# Power_2.net
KiCad netlist of a schematic drawn in Altium Designer
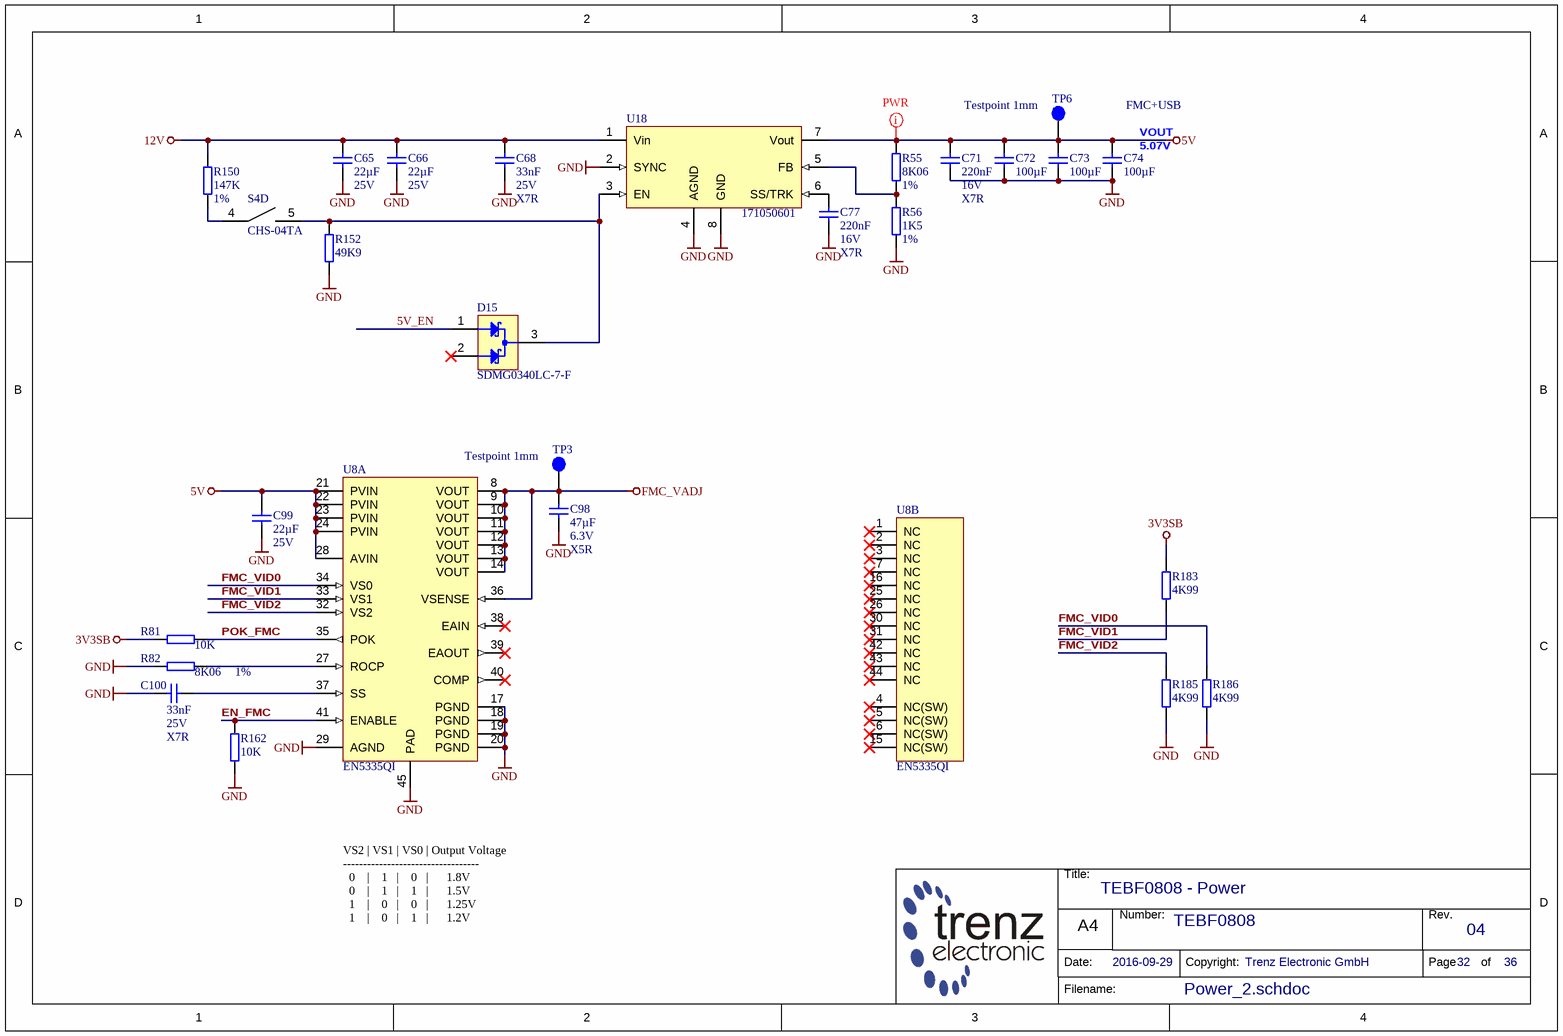
[diagram p0: Power_2.schdoc]

(export (version "E")
  (design (tool "Eeschema 10.0.6"))
  (components
    (comp (ref "C65")
      (value "22µF")
      (footprint "CAPC3216X180N")
      (description "KON 22µF X5R 25V SMD 10%")
      (fields (field (name "VOLTAGE") "25V") (field (name "TOLERANCE") "10%"))
      (libsource (lib "TE") (part "CAP-NP"))
    )
    (comp (ref "C66")
      (value "22µF")
      (footprint "CAPC3216X180N")
      (description "KON 22µF X5R 25V SMD 10%")
      (fields (field (name "VOLTAGE") "25V") (field (name "TOLERANCE") "10%"))
      (libsource (lib "TE") (part "CAP-NP"))
    )
    (comp (ref "C68")
      (value "33nF")
      (footprint "CAPC1005X55N")
      (description "KON 33nF 25V X7R SMD")
      (fields (field (name "VOLTAGE") "25V") (field (name "TECHNOLOGY") "X7R"))
      (libsource (lib "TE") (part "CAP-NP"))
    )
    (comp (ref "C71")
      (value "220nF")
      (footprint "CAPC1005X55N")
      (description "KON 220nF 16V X7R SMD")
      (fields (field (name "VOLTAGE") "16V") (field (name "TECHNOLOGY") "X7R"))
      (libsource (lib "TE") (part "CAP-NP"))
    )
    (comp (ref "C72")
      (value "100µF")
      (footprint "CAPC3216X180N")
      (description "KON 100µF 6,3V X5R SMD 20%")
      (fields (field (name "TOLERANCE") "20%") (field (name "VOLTAGE") "6.3V"))
      (libsource (lib "TE") (part "CAP-NP"))
    )
    (comp (ref "C73")
      (value "100µF")
      (footprint "CAPC3216X180N")
      (description "KON 100µF 6,3V X5R SMD 20%")
      (fields (field (name "TOLERANCE") "20%") (field (name "VOLTAGE") "6.3V"))
      (libsource (lib "TE") (part "CAP-NP"))
    )
    (comp (ref "C74")
      (value "100µF")
      (footprint "CAPC3216X180N")
      (description "KON 100µF 6,3V X5R SMD 20%")
      (fields (field (name "TOLERANCE") "20%") (field (name "VOLTAGE") "6.3V"))
      (libsource (lib "TE") (part "CAP-NP"))
    )
    (comp (ref "C77")
      (value "220nF")
      (footprint "CAPC1005X55N")
      (description "KON 220nF 16V X7R SMD")
      (fields (field (name "VOLTAGE") "16V") (field (name "TECHNOLOGY") "X7R"))
      (libsource (lib "TE") (part "CAP-NP"))
    )
    (comp (ref "C98")
      (value "47µF")
      (footprint "CAPC3216X180N")
      (description "KON 47µF 6.3V  X5R SMD 20%")
      (fields
        (field (name "VOLTAGE") "6.3V")
        (field (name "TECHNOLOGY") "X5R")
        (field (name "TOLERANCE") "20%")
      )
      (libsource (lib "TE") (part "CAP-NP"))
    )
    (comp (ref "C99")
      (value "22µF")
      (footprint "CAPC3216X180N")
      (description "KON 22µF X5R 25V SMD 10%")
      (fields (field (name "VOLTAGE") "25V") (field (name "TOLERANCE") "10%"))
      (libsource (lib "TE") (part "CAP-NP"))
    )
    (comp (ref "C100")
      (value "33nF")
      (footprint "CAPC1005X55N")
      (description "KON 33nF 25V X7R SMD")
      (fields (field (name "VOLTAGE") "25V") (field (name "TECHNOLOGY") "X7R"))
      (libsource (lib "TE") (part "CAP-NP"))
    )
    (comp (ref "D15")
      (value "SDMG0340LC-7-F")
      (footprint "SOT65P210X110-3N")
      (libsource (lib "TE") (part "SDMG0340LC"))
    )
    (comp (ref "R55")
      (value "8K06")
      (footprint "RESC1005X40N")
      (description "WID SMD 8K06 1% 0,063W")
      (fields (field (name "TOLERANCE") "1%"))
      (libsource (lib "TE") (part "RES"))
    )
    (comp (ref "R56")
      (value "1K5")
      (footprint "RESC1005X40N")
      (description "WID SMD 1K5 1% 0,063W")
      (fields (field (name "TOLERANCE") "1%"))
      (libsource (lib "TE") (part "RES"))
    )
    (comp (ref "R81")
      (value "10K")
      (footprint "RESC1005X40N")
      (description "WID SMD 10K 1% 0,063W")
      (fields (field (name "TOLERANCE") "1%"))
      (libsource (lib "TE") (part "RES"))
    )
    (comp (ref "R82")
      (value "8K06")
      (footprint "RESC1005X40N")
      (description "WID SMD 8K06 1% 0,063W")
      (fields (field (name "TOLERANCE") "1%"))
      (libsource (lib "TE") (part "RES"))
    )
    (comp (ref "R150")
      (value "147K")
      (footprint "RESC1005X40N")
      (description "WID SMD 147K 1% 0,063W")
      (fields (field (name "TOLERANCE") "1%"))
      (libsource (lib "TE") (part "RES"))
    )
    (comp (ref "R152")
      (value "49K9")
      (footprint "RESC1005X40N")
      (description "WID SMD 49K9 1% 0,063W")
      (fields (field (name "TOLERANCE") "1%"))
      (libsource (lib "TE") (part "RES"))
    )
    (comp (ref "R162")
      (value "10K")
      (footprint "RESC1005X40N")
      (description "WID SMD 10K 1% 0,063W")
      (fields (field (name "TOLERANCE") "1%"))
      (libsource (lib "TE") (part "RES"))
    )
    (comp (ref "R183")
      (value "4K99")
      (footprint "RESC1005X40N")
      (description "WID SMD 4K99 1% 0,063W")
      (fields (field (name "TOLERANCE") "1%"))
      (libsource (lib "TE") (part "RES"))
    )
    (comp (ref "R185")
      (value "4K99")
      (footprint "RESC1005X40N")
      (description "WID SMD 4K99 1% 0,063W")
      (fields (field (name "TOLERANCE") "1%"))
      (libsource (lib "TE") (part "RES"))
    )
    (comp (ref "R186")
      (value "4K99")
      (footprint "RESC1005X40N")
      (description "WID SMD 4K99 1% 0,063W")
      (fields (field (name "TOLERANCE") "1%"))
      (libsource (lib "TE") (part "RES"))
    )
    (comp (ref "S4")
      (value "CHS-04TA")
      (footprint "CHS-04TA")
      (description "DIP Schalter 4 fach 1,27mm SMD")
      (libsource (lib "TE") (part "CHS-04TA"))
    )
    (comp (ref "TP3") (value "Testpoint 1mm") (footprint "TP_1mm") (libsource (lib "TE") (part "TP")))
    (comp (ref "TP6") (value "Testpoint 1mm") (footprint "TP_1mm") (libsource (lib "TE") (part "TP")))
    (comp (ref "U8") (value "EN5335QI") (footprint "EN5335QI") (libsource (lib "TE") (part "EN5335QI")))
    (comp (ref "U18")
      (value "171050601")
      (footprint "7TO-PMOD")
      (libsource (lib "TE") (part "WE-DCDC-171050601"))
    )
  )
  (nets
    (net (code "1") (name "/5V_EN") (class "Default")
      (node (ref "D15") (pin "1") (pinfunction "A_1") (pintype "passive"))
    )
    (net (code "2") (name "/EN_FMC") (class "Default")
      (node (ref "R162") (pin "2") (pinfunction "2_2") (pintype "passive"))
      (node (ref "U8") (pin "41") (pinfunction "ENABLE_41") (pintype "input"))
    )
    (net (code "3") (name "/FMC_VID0") (class "Default")
      (node (ref "R186") (pin "1") (pinfunction "1_1") (pintype "passive"))
      (node (ref "U8") (pin "34") (pinfunction "VS0_34") (pintype "input"))
    )
    (net (code "4") (name "/FMC_VID1") (class "Default")
      (node (ref "R183") (pin "2") (pinfunction "2_2") (pintype "passive"))
      (node (ref "U8") (pin "33") (pinfunction "VS1_33") (pintype "input"))
    )
    (net (code "5") (name "/FMC_VID2") (class "Default")
      (node (ref "R185") (pin "1") (pinfunction "1_1") (pintype "passive"))
      (node (ref "U8") (pin "32") (pinfunction "VS2_32") (pintype "input"))
    )
    (net (code "6") (name "/POK_FMC") (class "Default")
      (node (ref "R81") (pin "2") (pinfunction "2_2") (pintype "passive"))
      (node (ref "U8") (pin "35") (pinfunction "POK_35") (pintype "output"))
    )
    (net (code "7") (name "3V3SB") (class "Default")
      (node (ref "R183") (pin "1") (pinfunction "1_1") (pintype "passive"))
      (node (ref "R81") (pin "1") (pinfunction "1_1") (pintype "passive"))
    )
    (net (code "8") (name "5V") (class "Default")
      (node (ref "C71") (pin "1") (pinfunction "1_1") (pintype "passive"))
      (node (ref "C72") (pin "1") (pinfunction "1_1") (pintype "passive"))
      (node (ref "C73") (pin "1") (pinfunction "1_1") (pintype "passive"))
      (node (ref "C74") (pin "1") (pinfunction "1_1") (pintype "passive"))
      (node (ref "C99") (pin "2") (pinfunction "2_2") (pintype "passive"))
      (node (ref "R55") (pin "1") (pinfunction "1_1") (pintype "passive"))
      (node (ref "TP6") (pin "1") (pintype "passive"))
      (node (ref "U18") (pin "7") (pinfunction "Vout_7") (pintype "power_in"))
      (node (ref "U8") (pin "21") (pinfunction "PVIN_21") (pintype "power_in"))
      (node (ref "U8") (pin "22") (pinfunction "PVIN_22") (pintype "power_in"))
      (node (ref "U8") (pin "23") (pinfunction "PVIN_23") (pintype "power_in"))
      (node (ref "U8") (pin "24") (pinfunction "PVIN_24") (pintype "power_in"))
      (node (ref "U8") (pin "28") (pinfunction "AVIN_28") (pintype "power_in"))
    )
    (net (code "9") (name "12V") (class "Default")
      (node (ref "C65") (pin "2") (pinfunction "2_2") (pintype "passive"))
      (node (ref "C66") (pin "2") (pinfunction "2_2") (pintype "passive"))
      (node (ref "C68") (pin "1") (pinfunction "1_1") (pintype "passive"))
      (node (ref "R150") (pin "2") (pinfunction "2_2") (pintype "passive"))
      (node (ref "U18") (pin "1") (pinfunction "Vin_1") (pintype "power_in"))
    )
    (net (code "10") (name "FMC_VADJ") (class "Default")
      (node (ref "C98") (pin "1") (pinfunction "1_1") (pintype "passive"))
      (node (ref "TP3") (pin "1") (pintype "passive"))
      (node (ref "U8") (pin "10") (pinfunction "VOUT_10") (pintype "power_in"))
      (node (ref "U8") (pin "11") (pinfunction "VOUT_11") (pintype "power_in"))
      (node (ref "U8") (pin "12") (pinfunction "VOUT_12") (pintype "power_in"))
      (node (ref "U8") (pin "13") (pinfunction "VOUT_13") (pintype "power_in"))
      (node (ref "U8") (pin "14") (pinfunction "VOUT_14") (pintype "power_in"))
      (node (ref "U8") (pin "36") (pinfunction "VSENSE_36") (pintype "input"))
      (node (ref "U8") (pin "8") (pinfunction "VOUT_8") (pintype "power_in"))
      (node (ref "U8") (pin "9") (pinfunction "VOUT_9") (pintype "power_in"))
    )
    (net (code "11") (name "GND") (class "Default")
      (node (ref "C100") (pin "1") (pinfunction "1_1") (pintype "passive"))
      (node (ref "C65") (pin "1") (pinfunction "1_1") (pintype "passive"))
      (node (ref "C66") (pin "1") (pinfunction "1_1") (pintype "passive"))
      (node (ref "C68") (pin "2") (pinfunction "2_2") (pintype "passive"))
      (node (ref "C71") (pin "2") (pinfunction "2_2") (pintype "passive"))
      (node (ref "C72") (pin "2") (pinfunction "2_2") (pintype "passive"))
      (node (ref "C73") (pin "2") (pinfunction "2_2") (pintype "passive"))
      (node (ref "C74") (pin "2") (pinfunction "2_2") (pintype "passive"))
      (node (ref "C77") (pin "2") (pinfunction "2_2") (pintype "passive"))
      (node (ref "C98") (pin "2") (pinfunction "2_2") (pintype "passive"))
      (node (ref "C99") (pin "1") (pinfunction "1_1") (pintype "passive"))
      (node (ref "R152") (pin "2") (pinfunction "2_2") (pintype "passive"))
      (node (ref "R162") (pin "1") (pinfunction "1_1") (pintype "passive"))
      (node (ref "R185") (pin "2") (pinfunction "2_2") (pintype "passive"))
      (node (ref "R186") (pin "2") (pinfunction "2_2") (pintype "passive"))
      (node (ref "R56") (pin "2") (pinfunction "2_2") (pintype "passive"))
      (node (ref "R82") (pin "1") (pinfunction "1_1") (pintype "passive"))
      (node (ref "U18") (pin "2") (pinfunction "SYNC_2") (pintype "input"))
      (node (ref "U18") (pin "4") (pinfunction "AGND_4") (pintype "power_in"))
      (node (ref "U18") (pin "8") (pinfunction "GND_8") (pintype "power_in"))
      (node (ref "U8") (pin "17") (pinfunction "PGND_17") (pintype "power_in"))
      (node (ref "U8") (pin "18") (pinfunction "PGND_18") (pintype "power_in"))
      (node (ref "U8") (pin "19") (pinfunction "PGND_19") (pintype "power_in"))
      (node (ref "U8") (pin "20") (pinfunction "PGND_20") (pintype "power_in"))
      (node (ref "U8") (pin "29") (pinfunction "AGND_29") (pintype "power_in"))
      (node (ref "U8") (pin "45") (pinfunction "PAD_45") (pintype "passive"))
    )
    (net (code "12") (name "Net-(D15-K)") (class "Default")
      (node (ref "D15") (pin "3") (pinfunction "K_3") (pintype "passive"))
      (node (ref "R152") (pin "1") (pinfunction "1_1") (pintype "passive"))
      (node (ref "S4") (pin "5") (pinfunction "5_5") (pintype "passive"))
      (node (ref "U18") (pin "3") (pinfunction "EN_3") (pintype "input"))
    )
    (net (code "13") (name "Net-(R150-Pad1)") (class "Default")
      (node (ref "R150") (pin "1") (pinfunction "1_1") (pintype "passive"))
      (node (ref "S4") (pin "4") (pinfunction "4_4") (pintype "passive"))
    )
    (net (code "14") (name "Net-(U8A-ROCP)") (class "Default")
      (node (ref "R82") (pin "2") (pinfunction "2_2") (pintype "passive"))
      (node (ref "U8") (pin "27") (pinfunction "ROCP_27") (pintype "input"))
    )
    (net (code "15") (name "Net-(U8A-SS)") (class "Default")
      (node (ref "C100") (pin "2") (pinfunction "2_2") (pintype "passive"))
      (node (ref "U8") (pin "37") (pinfunction "SS_37") (pintype "input"))
    )
    (net (code "16") (name "Net-(U18-FB)") (class "Default")
      (node (ref "R55") (pin "2") (pinfunction "2_2") (pintype "passive"))
      (node (ref "R56") (pin "1") (pinfunction "1_1") (pintype "passive"))
      (node (ref "U18") (pin "5") (pinfunction "FB_5") (pintype "input"))
    )
    (net (code "17") (name "Net-(U18-SS{slash}TRK)") (class "Default")
      (node (ref "C77") (pin "1") (pinfunction "1_1") (pintype "passive"))
      (node (ref "U18") (pin "6") (pinfunction "SS/TRK_6") (pintype "input"))
    )
    (net (code "18") (name "unconnected-(D15-A-Pad2)") (class "Default")
      (node (ref "D15") (pin "2") (pinfunction "A_2") (pintype "passive+no_connect"))
    )
    (net (code "19") (name "unconnected-(U8A-COMP-Pad40)") (class "Default")
      (node (ref "U8") (pin "40") (pinfunction "COMP_40") (pintype "output+no_connect"))
    )
    (net (code "20") (name "unconnected-(U8A-EAIN-Pad38)") (class "Default")
      (node (ref "U8") (pin "38") (pinfunction "EAIN_38") (pintype "input+no_connect"))
    )
    (net (code "21") (name "unconnected-(U8A-EAOUT-Pad39)") (class "Default")
      (node (ref "U8") (pin "39") (pinfunction "EAOUT_39") (pintype "output+no_connect"))
    )
    (net (code "22") (name "unconnected-(U8B-NC(SW)-Pad4)") (class "Default")
      (node (ref "U8") (pin "4") (pinfunction "NC(SW)_4") (pintype "passive+no_connect"))
    )
    (net (code "23") (name "unconnected-(U8B-NC(SW)-Pad5)") (class "Default")
      (node (ref "U8") (pin "5") (pinfunction "NC(SW)_5") (pintype "passive+no_connect"))
    )
    (net (code "24") (name "unconnected-(U8B-NC(SW)-Pad6)") (class "Default")
      (node (ref "U8") (pin "6") (pinfunction "NC(SW)_6") (pintype "passive+no_connect"))
    )
    (net (code "25") (name "unconnected-(U8B-NC(SW)-Pad15)") (class "Default")
      (node (ref "U8") (pin "15") (pinfunction "NC(SW)_15") (pintype "passive+no_connect"))
    )
    (net (code "26") (name "unconnected-(U8B-NC-Pad1)") (class "Default")
      (node (ref "U8") (pin "1") (pinfunction "NC_1") (pintype "passive+no_connect"))
    )
    (net (code "27") (name "unconnected-(U8B-NC-Pad2)") (class "Default")
      (node (ref "U8") (pin "2") (pinfunction "NC_2") (pintype "passive+no_connect"))
    )
    (net (code "28") (name "unconnected-(U8B-NC-Pad3)") (class "Default")
      (node (ref "U8") (pin "3") (pinfunction "NC_3") (pintype "passive+no_connect"))
    )
    (net (code "29") (name "unconnected-(U8B-NC-Pad7)") (class "Default")
      (node (ref "U8") (pin "7") (pinfunction "NC_7") (pintype "passive+no_connect"))
    )
    (net (code "30") (name "unconnected-(U8B-NC-Pad16)") (class "Default")
      (node (ref "U8") (pin "16") (pinfunction "NC_16") (pintype "passive+no_connect"))
    )
    (net (code "31") (name "unconnected-(U8B-NC-Pad25)") (class "Default")
      (node (ref "U8") (pin "25") (pinfunction "NC_25") (pintype "passive+no_connect"))
    )
    (net (code "32") (name "unconnected-(U8B-NC-Pad26)") (class "Default")
      (node (ref "U8") (pin "26") (pinfunction "NC_26") (pintype "passive+no_connect"))
    )
    (net (code "33") (name "unconnected-(U8B-NC-Pad30)") (class "Default")
      (node (ref "U8") (pin "30") (pinfunction "NC_30") (pintype "passive+no_connect"))
    )
    (net (code "34") (name "unconnected-(U8B-NC-Pad31)") (class "Default")
      (node (ref "U8") (pin "31") (pinfunction "NC_31") (pintype "passive+no_connect"))
    )
    (net (code "35") (name "unconnected-(U8B-NC-Pad42)") (class "Default")
      (node (ref "U8") (pin "42") (pinfunction "NC_42") (pintype "passive+no_connect"))
    )
    (net (code "36") (name "unconnected-(U8B-NC-Pad43)") (class "Default")
      (node (ref "U8") (pin "43") (pinfunction "NC_43") (pintype "passive+no_connect"))
    )
    (net (code "37") (name "unconnected-(U8B-NC-Pad44)") (class "Default")
      (node (ref "U8") (pin "44") (pinfunction "NC_44") (pintype "passive+no_connect"))
    )
  )
)
